# 07_CAN.net
KiCad netlist of a schematic drawn in Altium Designer
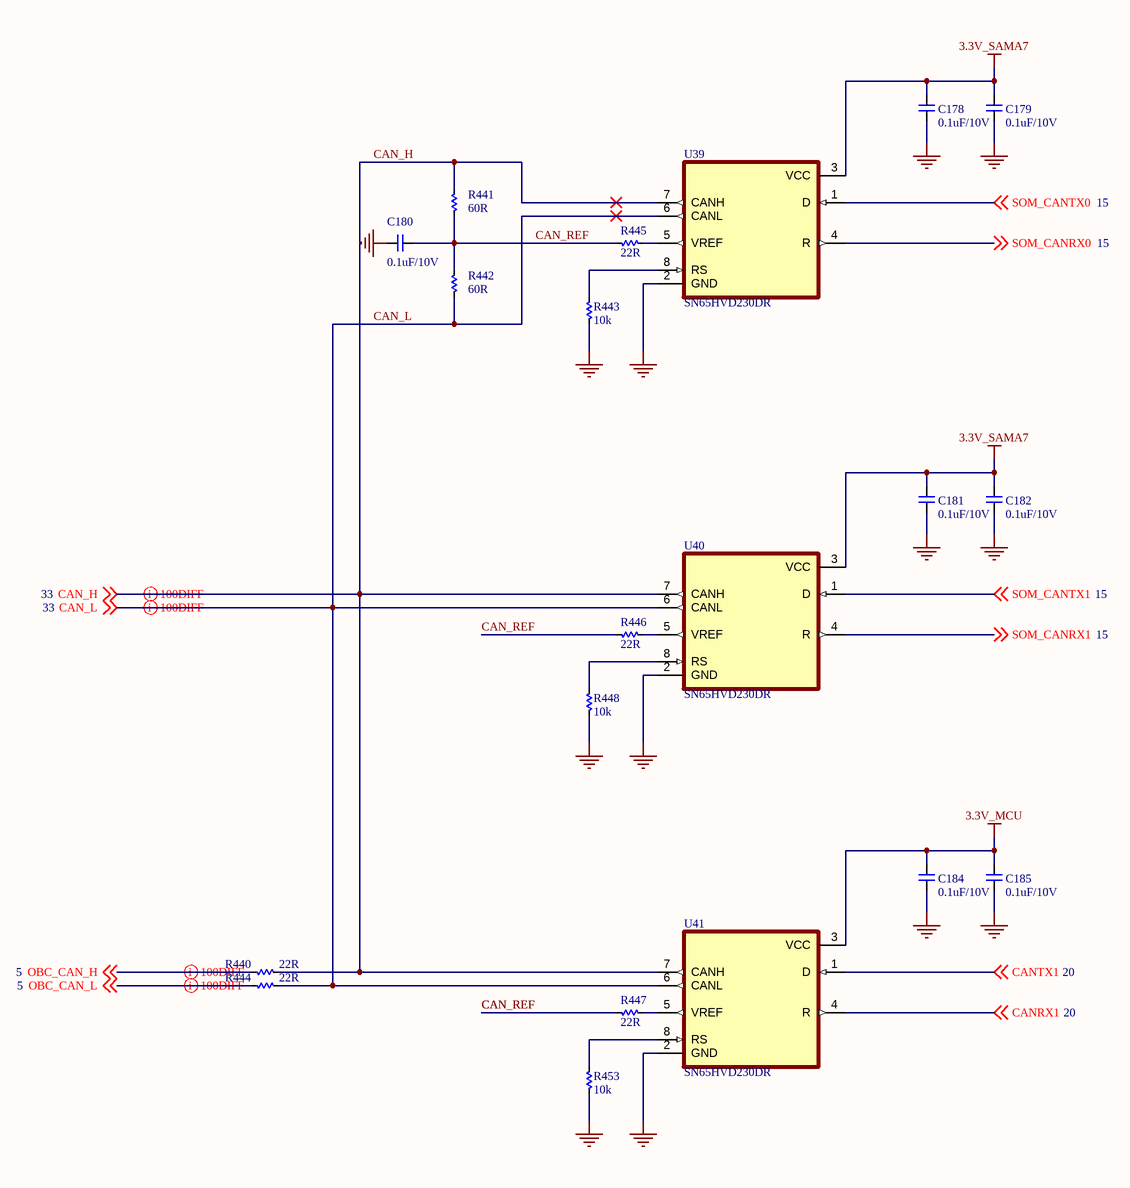
[diagram p0: 07_CAN.SchDoc]

(export (version "E")
  (design (tool "Eeschema 10.0.6"))
  (components
    (comp (ref "C178")
      (value "0.1uF/10V")
      (footprint "CAP_C_1005X60")
      (description "CAP")
      (libsource (lib "LABLIB") (part "_CAP_C_2"))
    )
    (comp (ref "C179")
      (value "0.1uF/10V")
      (footprint "CAP_C_1005X60")
      (description "CAP")
      (libsource (lib "LABLIB") (part "_CAP_C_2"))
    )
    (comp (ref "C180")
      (value "0.1uF/10V")
      (footprint "CAP_C_1005X60")
      (description "CAP")
      (libsource (lib "LABLIB") (part "_CAP_C_2"))
    )
    (comp (ref "C181")
      (value "0.1uF/10V")
      (footprint "CAP_C_1005X60")
      (description "CAP")
      (libsource (lib "LABLIB") (part "_CAP_C_2"))
    )
    (comp (ref "C182")
      (value "0.1uF/10V")
      (footprint "CAP_C_1005X60")
      (description "CAP")
      (libsource (lib "LABLIB") (part "_CAP_C_2"))
    )
    (comp (ref "C184")
      (value "0.1uF/10V")
      (footprint "CAP_C_1005X60")
      (description "CAP")
      (libsource (lib "LABLIB") (part "_CAP_C_2"))
    )
    (comp (ref "C185")
      (value "0.1uF/10V")
      (footprint "CAP_C_1005X60")
      (description "CAP")
      (libsource (lib "LABLIB") (part "_CAP_C_2"))
    )
    (comp (ref "R440")
      (value "22R")
      (footprint "RES_C_1005X40")
      (description "RES")
      (libsource (lib "LABLIB") (part "_RES_B_2"))
    )
    (comp (ref "R441")
      (value "60R")
      (footprint "RES_C_1005X40")
      (description "RES")
      (libsource (lib "LABLIB") (part "_RES_B_2"))
    )
    (comp (ref "R442")
      (value "60R")
      (footprint "RES_C_1005X40")
      (description "RES")
      (libsource (lib "LABLIB") (part "_RES_B_2"))
    )
    (comp (ref "R443")
      (value "10k")
      (footprint "RES_C_1005X40")
      (description "RES")
      (libsource (lib "LABLIB") (part "_RES_B_2"))
    )
    (comp (ref "R444")
      (value "22R")
      (footprint "RES_C_1005X40")
      (description "RES")
      (libsource (lib "LABLIB") (part "_RES_B_2"))
    )
    (comp (ref "R445")
      (value "22R")
      (footprint "RES_C_1005X40")
      (description "RES")
      (libsource (lib "LABLIB") (part "_RES_B_2"))
    )
    (comp (ref "R446")
      (value "22R")
      (footprint "RES_C_1005X40")
      (description "RES")
      (libsource (lib "LABLIB") (part "_RES_B_2"))
    )
    (comp (ref "R447")
      (value "22R")
      (footprint "RES_C_1005X40")
      (description "RES")
      (libsource (lib "LABLIB") (part "_RES_B_2"))
    )
    (comp (ref "R448")
      (value "10k")
      (footprint "RES_C_1005X40")
      (description "RES")
      (libsource (lib "LABLIB") (part "_RES_B_2"))
    )
    (comp (ref "R453")
      (value "10k")
      (footprint "RES_C_1005X40")
      (description "RES")
      (libsource (lib "LABLIB") (part "_RES_B_2"))
    )
    (comp (ref "U39")
      (value "SN65HVD230DR")
      (footprint "SOIC127P600X175-8N")
      (description "3.3 V CAN Transceiver with Standby Mode")
      (fields (field (name "MF") "Texas Instruments"))
      (libsource (lib "COMM_SCHLIB") (part "SN65HVD230DR"))
    )
    (comp (ref "U40")
      (value "SN65HVD230DR")
      (footprint "SOIC127P600X175-8N")
      (description "3.3 V CAN Transceiver with Standby Mode")
      (fields (field (name "MF") "Texas Instruments"))
      (libsource (lib "COMM_SCHLIB") (part "SN65HVD230DR"))
    )
    (comp (ref "U41")
      (value "SN65HVD230DR")
      (footprint "SOIC127P600X175-8N")
      (description "3.3 V CAN Transceiver with Standby Mode")
      (fields (field (name "MF") "Texas Instruments"))
      (libsource (lib "COMM_SCHLIB") (part "SN65HVD230DR"))
    )
  )
  (nets
    (net (code "1") (name "/CAN_REF") (class "Default")
      (node (ref "C180") (pin "1") (pinfunction "1_1") (pintype "passive"))
      (node (ref "R441") (pin "1") (pinfunction "1_1") (pintype "passive"))
      (node (ref "R442") (pin "2") (pinfunction "2_2") (pintype "passive"))
      (node (ref "R445") (pin "1") (pinfunction "1_1") (pintype "passive"))
      (node (ref "R446") (pin "1") (pinfunction "1_1") (pintype "passive"))
      (node (ref "R447") (pin "1") (pinfunction "1_1") (pintype "passive"))
    )
    (net (code "2") (name "3.3V_MCU") (class "Default")
      (node (ref "C184") (pin "1") (pinfunction "1_1") (pintype "passive"))
      (node (ref "C185") (pin "1") (pinfunction "1_1") (pintype "passive"))
      (node (ref "U41") (pin "3") (pinfunction "VCC_3") (pintype "power_in"))
    )
    (net (code "3") (name "3.3V_SAMA7") (class "Default")
      (node (ref "C178") (pin "1") (pinfunction "1_1") (pintype "passive"))
      (node (ref "C179") (pin "1") (pinfunction "1_1") (pintype "passive"))
      (node (ref "C181") (pin "1") (pinfunction "1_1") (pintype "passive"))
      (node (ref "C182") (pin "1") (pinfunction "1_1") (pintype "passive"))
      (node (ref "U39") (pin "3") (pinfunction "VCC_3") (pintype "power_in"))
      (node (ref "U40") (pin "3") (pinfunction "VCC_3") (pintype "power_in"))
    )
    (net (code "4") (name "CANRX1") (class "Default")
      (node (ref "U41") (pin "4") (pinfunction "R_4") (pintype "output"))
    )
    (net (code "5") (name "CANTX1") (class "Default")
      (node (ref "U41") (pin "1") (pinfunction "D_1") (pintype "input"))
    )
    (net (code "6") (name "CAN_H") (class "Default")
      (node (ref "R440") (pin "2") (pinfunction "2_2") (pintype "passive"))
      (node (ref "R441") (pin "2") (pinfunction "2_2") (pintype "passive"))
      (node (ref "U39") (pin "7") (pinfunction "CANH_7") (pintype "output"))
      (node (ref "U40") (pin "7") (pinfunction "CANH_7") (pintype "output"))
      (node (ref "U41") (pin "7") (pinfunction "CANH_7") (pintype "output"))
    )
    (net (code "7") (name "CAN_L") (class "Default")
      (node (ref "R442") (pin "1") (pinfunction "1_1") (pintype "passive"))
      (node (ref "R444") (pin "2") (pinfunction "2_2") (pintype "passive"))
      (node (ref "U39") (pin "6") (pinfunction "CANL_6") (pintype "output"))
      (node (ref "U40") (pin "6") (pinfunction "CANL_6") (pintype "output"))
      (node (ref "U41") (pin "6") (pinfunction "CANL_6") (pintype "output"))
    )
    (net (code "8") (name "GND") (class "Default")
      (node (ref "C178") (pin "2") (pinfunction "2_2") (pintype "passive"))
      (node (ref "C179") (pin "2") (pinfunction "2_2") (pintype "passive"))
      (node (ref "C180") (pin "2") (pinfunction "2_2") (pintype "passive"))
      (node (ref "C181") (pin "2") (pinfunction "2_2") (pintype "passive"))
      (node (ref "C182") (pin "2") (pinfunction "2_2") (pintype "passive"))
      (node (ref "C184") (pin "2") (pinfunction "2_2") (pintype "passive"))
      (node (ref "C185") (pin "2") (pinfunction "2_2") (pintype "passive"))
      (node (ref "R443") (pin "1") (pinfunction "1_1") (pintype "passive"))
      (node (ref "R448") (pin "1") (pinfunction "1_1") (pintype "passive"))
      (node (ref "R453") (pin "1") (pinfunction "1_1") (pintype "passive"))
      (node (ref "U39") (pin "2") (pinfunction "GND_2") (pintype "power_in"))
      (node (ref "U40") (pin "2") (pinfunction "GND_2") (pintype "power_in"))
      (node (ref "U41") (pin "2") (pinfunction "GND_2") (pintype "power_in"))
    )
    (net (code "9") (name "Net-(U39-RS)") (class "Default")
      (node (ref "R443") (pin "2") (pinfunction "2_2") (pintype "passive"))
      (node (ref "U39") (pin "8") (pinfunction "RS_8") (pintype "input"))
    )
    (net (code "10") (name "Net-(U39-VREF)") (class "Default")
      (node (ref "R445") (pin "2") (pinfunction "2_2") (pintype "passive"))
      (node (ref "U39") (pin "5") (pinfunction "VREF_5") (pintype "output"))
    )
    (net (code "11") (name "Net-(U40-RS)") (class "Default")
      (node (ref "R448") (pin "2") (pinfunction "2_2") (pintype "passive"))
      (node (ref "U40") (pin "8") (pinfunction "RS_8") (pintype "input"))
    )
    (net (code "12") (name "Net-(U40-VREF)") (class "Default")
      (node (ref "R446") (pin "2") (pinfunction "2_2") (pintype "passive"))
      (node (ref "U40") (pin "5") (pinfunction "VREF_5") (pintype "output"))
    )
    (net (code "13") (name "Net-(U41-RS)") (class "Default")
      (node (ref "R453") (pin "2") (pinfunction "2_2") (pintype "passive"))
      (node (ref "U41") (pin "8") (pinfunction "RS_8") (pintype "input"))
    )
    (net (code "14") (name "Net-(U41-VREF)") (class "Default")
      (node (ref "R447") (pin "2") (pinfunction "2_2") (pintype "passive"))
      (node (ref "U41") (pin "5") (pinfunction "VREF_5") (pintype "output"))
    )
    (net (code "15") (name "OBC_CAN_H") (class "Default")
      (node (ref "R440") (pin "1") (pinfunction "1_1") (pintype "passive"))
    )
    (net (code "16") (name "OBC_CAN_L") (class "Default")
      (node (ref "R444") (pin "1") (pinfunction "1_1") (pintype "passive"))
    )
    (net (code "17") (name "SOM_CANRX0") (class "Default")
      (node (ref "U39") (pin "4") (pinfunction "R_4") (pintype "output"))
    )
    (net (code "18") (name "SOM_CANRX1") (class "Default")
      (node (ref "U40") (pin "4") (pinfunction "R_4") (pintype "output"))
    )
    (net (code "19") (name "SOM_CANTX0") (class "Default")
      (node (ref "U39") (pin "1") (pinfunction "D_1") (pintype "input"))
    )
    (net (code "20") (name "SOM_CANTX1") (class "Default")
      (node (ref "U40") (pin "1") (pinfunction "D_1") (pintype "input"))
    )
  )
)
